# mainboard_transmitter_vf0_1.net
KiCad netlist of a schematic drawn in EAGLE
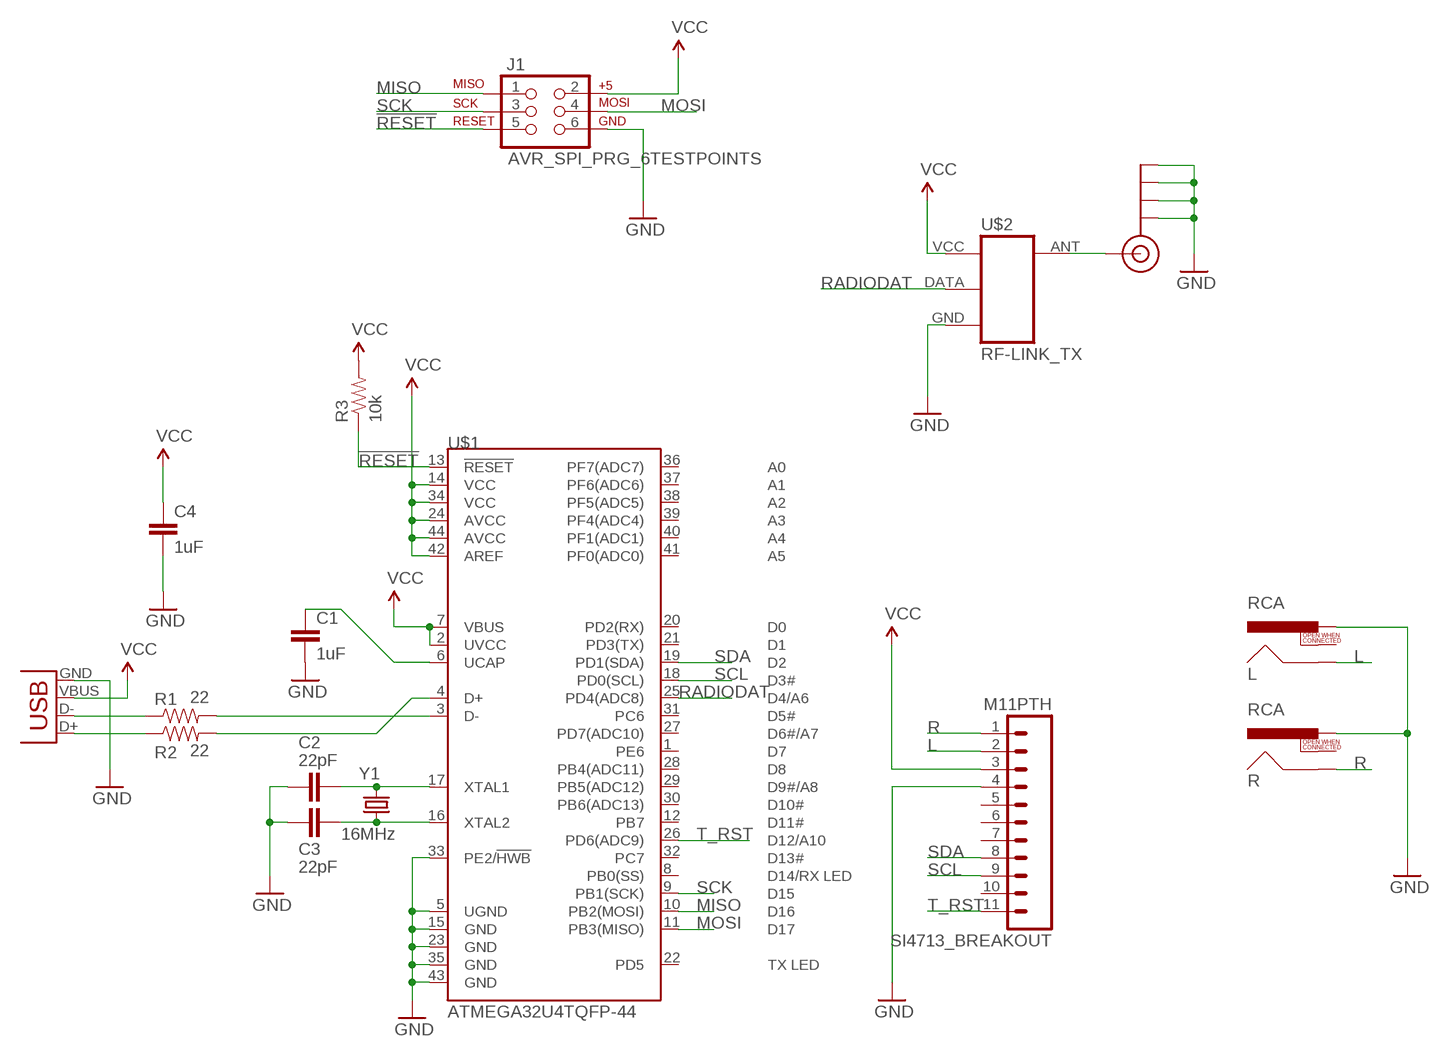
[diagram p0: schematic, sheet 1]

(export (version "E")
  (design (tool "Eeschema 10.0.6"))
  (components
    (comp (ref "C1")
      (value "1uF")
      (footprint "eagle-import:CAP-PTH-SMALL")
      (libsource (lib "eagle-import") (part "CAPPTH"))
    )
    (comp (ref "C2")
      (value "22pF")
      (footprint "eagle-import:CAP-PTH-SMALL")
      (libsource (lib "eagle-import") (part "CAPPTH"))
    )
    (comp (ref "C3")
      (value "22pF")
      (footprint "eagle-import:CAP-PTH-SMALL")
      (libsource (lib "eagle-import") (part "CAPPTH"))
    )
    (comp (ref "C4")
      (value "1uF")
      (footprint "eagle-import:CAP-PTH-SMALL")
      (libsource (lib "eagle-import") (part "CAPPTH"))
    )
    (comp (ref "J$1")
      (value "SMA_EDGE")
      (footprint "eagle-import:SMA-EDGE")
      (libsource (lib "eagle-import") (part "SMA_EDGE"))
    )
    (comp (ref "J1")
      (value "AVR_SPI_PRG_6TESTPOINTS")
      (footprint "eagle-import:2X3_TEST_POINTS")
      (libsource (lib "eagle-import") (part "AVR_SPI_PRG_6TESTPOINTS"))
    )
    (comp (ref "JP1")
      (value "USB-B")
      (footprint "eagle-import:USB-B-PTH")
      (libsource (lib "eagle-import") (part "USBPTH"))
    )
    (comp (ref "L")
      (value "RCA")
      (footprint "eagle-import:RCA")
      (libsource (lib "eagle-import") (part "RCA"))
    )
    (comp (ref "R")
      (value "RCA")
      (footprint "eagle-import:RCA")
      (libsource (lib "eagle-import") (part "RCA"))
    )
    (comp (ref "R1")
      (value "22")
      (footprint "eagle-import:AXIAL-0.1")
      (libsource (lib "eagle-import") (part "RESISTORPTH-1/4W-VERT"))
    )
    (comp (ref "R2")
      (value "22")
      (footprint "eagle-import:AXIAL-0.1")
      (libsource (lib "eagle-import") (part "RESISTORPTH-1/4W-VERT"))
    )
    (comp (ref "R3")
      (value "10k")
      (footprint "eagle-import:AXIAL-0.1")
      (libsource (lib "eagle-import") (part "10KOHM-1/4W5%(PTH)VERT"))
    )
    (comp (ref "SI4713_BREAKOUT")
      (value "M11PTH")
      (footprint "eagle-import:1X11")
      (libsource (lib "eagle-import") (part "M11PTH"))
    )
    (comp (ref "U$1")
      (value "ATMEGA32U4TQFP-44")
      (footprint "eagle-import:TQFP44")
      (libsource (lib "eagle-import") (part "ATMEGA32U4TQFP-44"))
    )
    (comp (ref "U$2")
      (value "RF-LINK_TX")
      (footprint "eagle-import:RF-LINK_TX")
      (libsource (lib "eagle-import") (part "RF-LINK_TX"))
    )
    (comp (ref "Y1")
      (value "16MHz")
      (footprint "eagle-import:HC49US")
      (libsource (lib "eagle-import") (part "CRYSTALHC49US"))
    )
  )
  (nets
    (net (code "1") (name "/L") (class "Default")
      (node (ref "L") (pin "SHELL") (pinfunction "SHELL_SHELL") (pintype "bidirectional"))
      (node (ref "SI4713_BREAKOUT") (pin "2") (pinfunction "2_2") (pintype "passive"))
    )
    (net (code "2") (name "/MISO") (class "Default")
      (node (ref "J1") (pin "1") (pinfunction "1_1") (pintype "passive"))
      (node (ref "U$1") (pin "10") (pinfunction "PB2(MOSI)_10") (pintype "bidirectional"))
    )
    (net (code "3") (name "/MOSI") (class "Default")
      (node (ref "J1") (pin "4") (pinfunction "4_4") (pintype "passive"))
      (node (ref "U$1") (pin "11") (pinfunction "PB3(MISO)_11") (pintype "bidirectional"))
    )
    (net (code "4") (name "/R") (class "Default")
      (node (ref "R") (pin "SHELL") (pinfunction "SHELL_SHELL") (pintype "bidirectional"))
      (node (ref "SI4713_BREAKOUT") (pin "1") (pinfunction "1_1") (pintype "passive"))
    )
    (net (code "5") (name "/RADIODAT") (class "Default")
      (node (ref "U$1") (pin "25") (pinfunction "PD4(ADC8)_25") (pintype "bidirectional"))
      (node (ref "U$2") (pin "DATA") (pinfunction "DATA_DATA") (pintype "input"))
    )
    (net (code "6") (name "/SCK") (class "Default")
      (node (ref "J1") (pin "3") (pinfunction "3_3") (pintype "passive"))
      (node (ref "U$1") (pin "9") (pinfunction "PB1(SCK)_9") (pintype "bidirectional"))
    )
    (net (code "7") (name "/SCL") (class "Default")
      (node (ref "SI4713_BREAKOUT") (pin "9") (pinfunction "9_9") (pintype "passive"))
      (node (ref "U$1") (pin "18") (pinfunction "PD0(SCL)_18") (pintype "bidirectional"))
    )
    (net (code "8") (name "/SDA") (class "Default")
      (node (ref "SI4713_BREAKOUT") (pin "8") (pinfunction "8_8") (pintype "passive"))
      (node (ref "U$1") (pin "19") (pinfunction "PD1(SDA)_19") (pintype "bidirectional"))
    )
    (net (code "9") (name "/T_RST") (class "Default")
      (node (ref "SI4713_BREAKOUT") (pin "11") (pinfunction "11_11") (pintype "passive"))
      (node (ref "U$1") (pin "26") (pinfunction "PD6(ADC9)_26") (pintype "bidirectional"))
    )
    (net (code "10") (name "/~{RESET}") (class "Default")
      (node (ref "J1") (pin "5") (pinfunction "5_5") (pintype "passive"))
      (node (ref "R3") (pin "P$1") (pinfunction "1_P$1") (pintype "passive"))
      (node (ref "U$1") (pin "13") (pinfunction "~{RESET}_13") (pintype "bidirectional"))
    )
    (net (code "11") (name "GND") (class "Default")
      (node (ref "C1") (pin "2") (pinfunction "2_2") (pintype "passive"))
      (node (ref "C2") (pin "1") (pinfunction "1_1") (pintype "passive"))
      (node (ref "C3") (pin "1") (pinfunction "1_1") (pintype "passive"))
      (node (ref "C4") (pin "2") (pinfunction "2_2") (pintype "passive"))
      (node (ref "J$1") (pin "GND@0") (pinfunction "GND_GND@0") (pintype "bidirectional"))
      (node (ref "J$1") (pin "GND@1") (pinfunction "GND_GND@1") (pintype "bidirectional"))
      (node (ref "J$1") (pin "GND@2") (pinfunction "GND_GND@2") (pintype "bidirectional"))
      (node (ref "J$1") (pin "GND@3") (pinfunction "GND_GND@3") (pintype "bidirectional"))
      (node (ref "J1") (pin "6") (pinfunction "6_6") (pintype "passive"))
      (node (ref "JP1") (pin "GND") (pinfunction "GND_GND") (pintype "bidirectional"))
      (node (ref "L") (pin "PIN") (pinfunction "PIN_PIN") (pintype "bidirectional"))
      (node (ref "R") (pin "PIN") (pinfunction "PIN_PIN") (pintype "bidirectional"))
      (node (ref "SI4713_BREAKOUT") (pin "4") (pinfunction "4_4") (pintype "passive"))
      (node (ref "U$1") (pin "15") (pinfunction "GND_15") (pintype "bidirectional"))
      (node (ref "U$1") (pin "23") (pinfunction "GND_23") (pintype "bidirectional"))
      (node (ref "U$1") (pin "33") (pinfunction "PE2/~{HWB}_33") (pintype "bidirectional"))
      (node (ref "U$1") (pin "35") (pinfunction "GND_35") (pintype "bidirectional"))
      (node (ref "U$1") (pin "43") (pinfunction "GND_43") (pintype "bidirectional"))
      (node (ref "U$1") (pin "5") (pinfunction "UGND_5") (pintype "bidirectional"))
      (node (ref "U$2") (pin "GND") (pinfunction "GND_GND") (pintype "power_in"))
    )
    (net (code "12") (name "Net-(J$1-SIGNAL)") (class "Default")
      (node (ref "J$1") (pin "SIG") (pinfunction "SIGNAL_SIG") (pintype "bidirectional"))
      (node (ref "U$2") (pin "ANT") (pinfunction "ANT_ANT") (pintype "passive"))
    )
    (net (code "13") (name "Net-(R1-1)") (class "Default")
      (node (ref "JP1") (pin "D-") (pinfunction "D-_D-") (pintype "bidirectional"))
      (node (ref "R1") (pin "P$1") (pinfunction "1_P$1") (pintype "passive"))
    )
    (net (code "14") (name "Net-(R1-2)") (class "Default")
      (node (ref "R1") (pin "P$2") (pinfunction "2_P$2") (pintype "passive"))
      (node (ref "U$1") (pin "3") (pinfunction "D-_3") (pintype "bidirectional"))
    )
    (net (code "15") (name "Net-(R2-1)") (class "Default")
      (node (ref "JP1") (pin "D+") (pinfunction "D+_D+") (pintype "bidirectional"))
      (node (ref "R2") (pin "P$1") (pinfunction "1_P$1") (pintype "passive"))
    )
    (net (code "16") (name "Net-(R2-2)") (class "Default")
      (node (ref "R2") (pin "P$2") (pinfunction "2_P$2") (pintype "passive"))
      (node (ref "U$1") (pin "4") (pinfunction "D+_4") (pintype "bidirectional"))
    )
    (net (code "17") (name "Net-(U$1-UCAP)") (class "Default")
      (node (ref "C1") (pin "1") (pinfunction "1_1") (pintype "passive"))
      (node (ref "U$1") (pin "6") (pinfunction "UCAP_6") (pintype "bidirectional"))
    )
    (net (code "18") (name "Net-(U$1-XTAL1)") (class "Default")
      (node (ref "C2") (pin "2") (pinfunction "2_2") (pintype "passive"))
      (node (ref "U$1") (pin "17") (pinfunction "XTAL1_17") (pintype "bidirectional"))
      (node (ref "Y1") (pin "2") (pinfunction "2_2") (pintype "passive"))
    )
    (net (code "19") (name "Net-(U$1-XTAL2)") (class "Default")
      (node (ref "C3") (pin "2") (pinfunction "2_2") (pintype "passive"))
      (node (ref "U$1") (pin "16") (pinfunction "XTAL2_16") (pintype "bidirectional"))
      (node (ref "Y1") (pin "1") (pinfunction "1_1") (pintype "passive"))
    )
    (net (code "20") (name "VCC") (class "Default")
      (node (ref "C4") (pin "1") (pinfunction "1_1") (pintype "passive"))
      (node (ref "J1") (pin "2") (pinfunction "2_2") (pintype "passive"))
      (node (ref "JP1") (pin "VBUS") (pinfunction "VBUS_VBUS") (pintype "bidirectional"))
      (node (ref "R3") (pin "P$2") (pinfunction "2_P$2") (pintype "passive"))
      (node (ref "SI4713_BREAKOUT") (pin "3") (pinfunction "3_3") (pintype "passive"))
      (node (ref "U$1") (pin "14") (pinfunction "VCC_14") (pintype "bidirectional"))
      (node (ref "U$1") (pin "2") (pinfunction "UVCC_2") (pintype "bidirectional"))
      (node (ref "U$1") (pin "24") (pinfunction "AVCC_24") (pintype "bidirectional"))
      (node (ref "U$1") (pin "34") (pinfunction "VCC_34") (pintype "bidirectional"))
      (node (ref "U$1") (pin "42") (pinfunction "AREF_42") (pintype "bidirectional"))
      (node (ref "U$1") (pin "44") (pinfunction "AVCC_44") (pintype "bidirectional"))
      (node (ref "U$1") (pin "7") (pinfunction "VBUS_7") (pintype "bidirectional"))
      (node (ref "U$2") (pin "VCC") (pinfunction "+5V_VCC") (pintype "power_in"))
    )
    (net (code "21") (name "unconnected-(L-PadSWITCH)") (class "Default")
      (node (ref "L") (pin "SWITCH") (pinfunction "SWITCH_SWITCH") (pintype "bidirectional"))
    )
    (net (code "22") (name "unconnected-(R-PadSWITCH)") (class "Default")
      (node (ref "R") (pin "SWITCH") (pinfunction "SWITCH_SWITCH") (pintype "bidirectional"))
    )
    (net (code "23") (name "unconnected-(SI4713_BREAKOUT-Pad5)") (class "Default")
      (node (ref "SI4713_BREAKOUT") (pin "5") (pinfunction "5_5") (pintype "passive"))
    )
    (net (code "24") (name "unconnected-(SI4713_BREAKOUT-Pad6)") (class "Default")
      (node (ref "SI4713_BREAKOUT") (pin "6") (pinfunction "6_6") (pintype "passive"))
    )
    (net (code "25") (name "unconnected-(SI4713_BREAKOUT-Pad7)") (class "Default")
      (node (ref "SI4713_BREAKOUT") (pin "7") (pinfunction "7_7") (pintype "passive"))
    )
    (net (code "26") (name "unconnected-(SI4713_BREAKOUT-Pad10)") (class "Default")
      (node (ref "SI4713_BREAKOUT") (pin "10") (pinfunction "10_10") (pintype "passive"))
    )
    (net (code "27") (name "unconnected-(U$1-PB0(SS)-Pad8)") (class "Default")
      (node (ref "U$1") (pin "8") (pinfunction "PB0(SS)_8") (pintype "bidirectional"))
    )
    (net (code "28") (name "unconnected-(U$1-PB4(ADC11)-Pad28)") (class "Default")
      (node (ref "U$1") (pin "28") (pinfunction "PB4(ADC11)_28") (pintype "bidirectional"))
    )
    (net (code "29") (name "unconnected-(U$1-PB5(ADC12)-Pad29)") (class "Default")
      (node (ref "U$1") (pin "29") (pinfunction "PB5(ADC12)_29") (pintype "bidirectional"))
    )
    (net (code "30") (name "unconnected-(U$1-PB6(ADC13)-Pad30)") (class "Default")
      (node (ref "U$1") (pin "30") (pinfunction "PB6(ADC13)_30") (pintype "bidirectional"))
    )
    (net (code "31") (name "unconnected-(U$1-PB7-Pad12)") (class "Default")
      (node (ref "U$1") (pin "12") (pinfunction "PB7_12") (pintype "bidirectional"))
    )
    (net (code "32") (name "unconnected-(U$1-PC6-Pad31)") (class "Default")
      (node (ref "U$1") (pin "31") (pinfunction "PC6_31") (pintype "bidirectional"))
    )
    (net (code "33") (name "unconnected-(U$1-PC7-Pad32)") (class "Default")
      (node (ref "U$1") (pin "32") (pinfunction "PC7_32") (pintype "bidirectional"))
    )
    (net (code "34") (name "unconnected-(U$1-PD2(RX)-Pad20)") (class "Default")
      (node (ref "U$1") (pin "20") (pinfunction "PD2(RX)_20") (pintype "bidirectional"))
    )
    (net (code "35") (name "unconnected-(U$1-PD3(TX)-Pad21)") (class "Default")
      (node (ref "U$1") (pin "21") (pinfunction "PD3(TX)_21") (pintype "bidirectional"))
    )
    (net (code "36") (name "unconnected-(U$1-PD5-Pad22)") (class "Default")
      (node (ref "U$1") (pin "22") (pinfunction "PD5_22") (pintype "bidirectional"))
    )
    (net (code "37") (name "unconnected-(U$1-PD7(ADC10)-Pad27)") (class "Default")
      (node (ref "U$1") (pin "27") (pinfunction "PD7(ADC10)_27") (pintype "bidirectional"))
    )
    (net (code "38") (name "unconnected-(U$1-PE6-Pad1)") (class "Default")
      (node (ref "U$1") (pin "1") (pinfunction "PE6_1") (pintype "bidirectional"))
    )
    (net (code "39") (name "unconnected-(U$1-PF0(ADC0)-Pad41)") (class "Default")
      (node (ref "U$1") (pin "41") (pinfunction "PF0(ADC0)_41") (pintype "bidirectional"))
    )
    (net (code "40") (name "unconnected-(U$1-PF1(ADC1)-Pad40)") (class "Default")
      (node (ref "U$1") (pin "40") (pinfunction "PF1(ADC1)_40") (pintype "bidirectional"))
    )
    (net (code "41") (name "unconnected-(U$1-PF4(ADC4)-Pad39)") (class "Default")
      (node (ref "U$1") (pin "39") (pinfunction "PF4(ADC4)_39") (pintype "bidirectional"))
    )
    (net (code "42") (name "unconnected-(U$1-PF5(ADC5)-Pad38)") (class "Default")
      (node (ref "U$1") (pin "38") (pinfunction "PF5(ADC5)_38") (pintype "bidirectional"))
    )
    (net (code "43") (name "unconnected-(U$1-PF6(ADC6)-Pad37)") (class "Default")
      (node (ref "U$1") (pin "37") (pinfunction "PF6(ADC6)_37") (pintype "bidirectional"))
    )
    (net (code "44") (name "unconnected-(U$1-PF7(ADC7)-Pad36)") (class "Default")
      (node (ref "U$1") (pin "36") (pinfunction "PF7(ADC7)_36") (pintype "bidirectional"))
    )
  )
)
